# design.net
KiCad netlist of a schematic drawn in Altium Designer
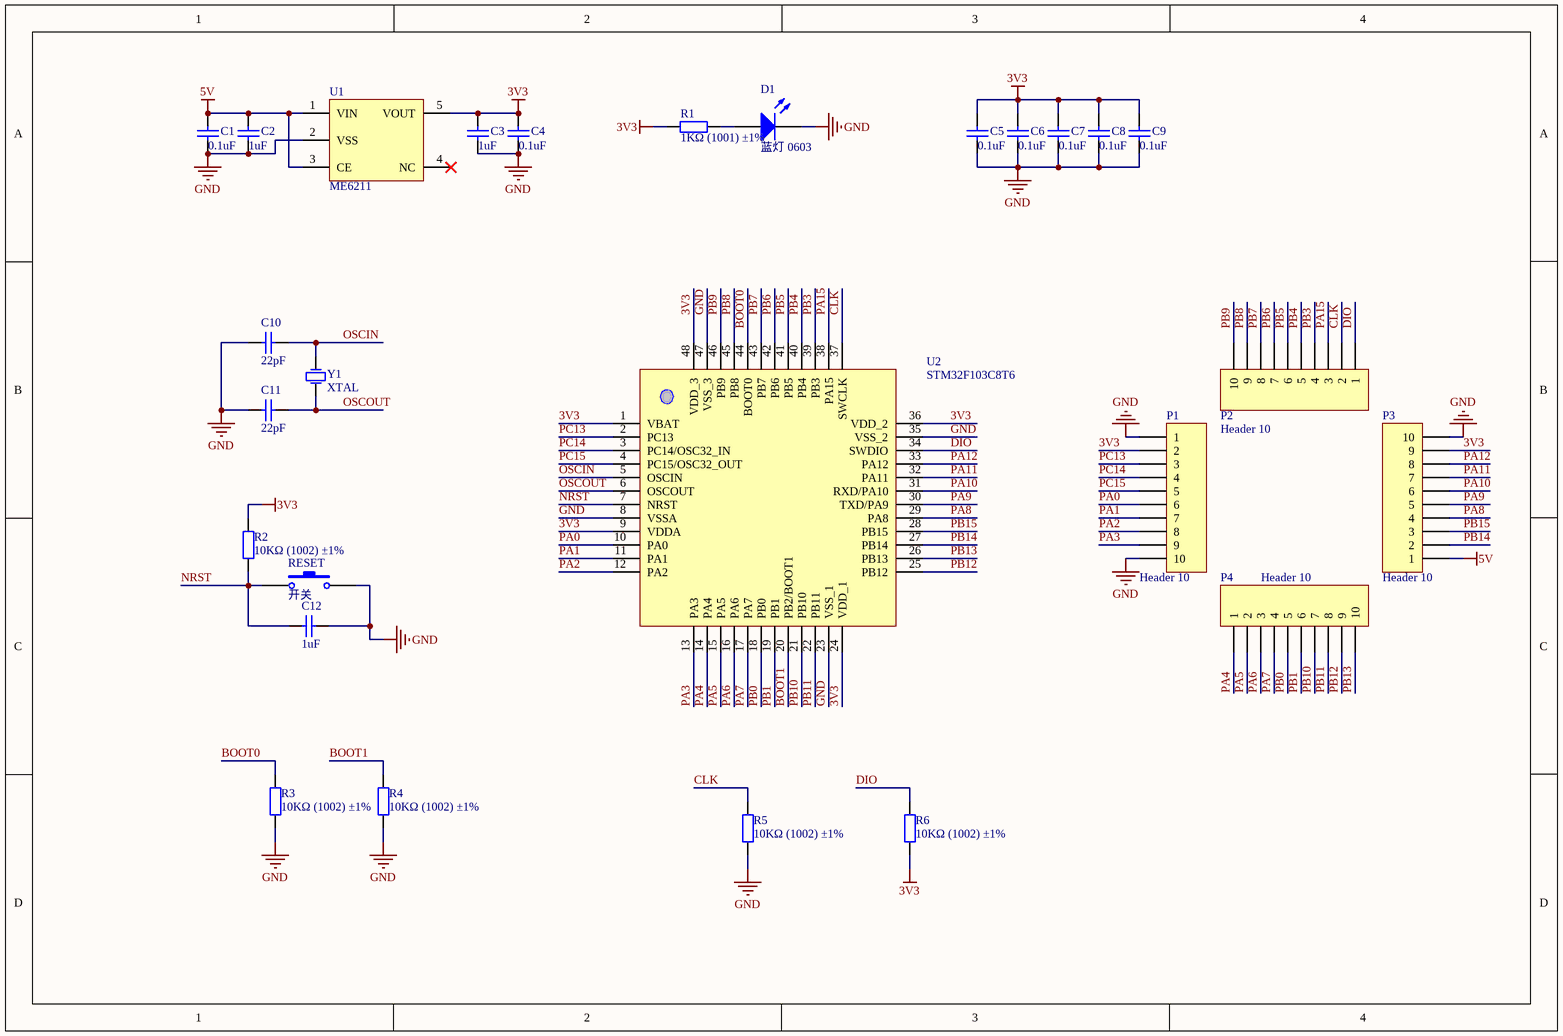
[diagram p0: 原理图.SchDoc]

(export (version "E")
  (design (tool "Eeschema 10.0.6"))
  (components
    (comp (ref "C1")
      (value "0.1uF")
      (footprint "0603_C")
      (description "贴片电容")
      (fields (field (name "Comment") "Cap"))
      (libsource (lib "Miscellaneous Devices LC (1)") (part "0603 1uF (105) 10% 50V"))
    )
    (comp (ref "C2")
      (value "1uF")
      (footprint "0603_C")
      (description "贴片电容")
      (fields (field (name "Comment") "Cap"))
      (libsource (lib "Miscellaneous Devices LC (1)") (part "0603 1uF (105) 10% 50V"))
    )
    (comp (ref "C3")
      (value "1uF")
      (footprint "0603_C")
      (description "贴片电容")
      (fields (field (name "Comment") "Cap"))
      (libsource (lib "Miscellaneous Devices LC (1)") (part "0603 1uF (105) 10% 50V"))
    )
    (comp (ref "C4")
      (value "0.1uF")
      (footprint "0603_C")
      (description "贴片电容")
      (fields (field (name "Comment") "Cap"))
      (libsource (lib "Miscellaneous Devices LC (1)") (part "0603 1uF (105) 10% 50V"))
    )
    (comp (ref "C5")
      (value "0.1uF")
      (footprint "0603_C")
      (description "贴片电容")
      (fields (field (name "Comment") "Cap"))
      (libsource (lib "Miscellaneous Devices LC (1)") (part "0603 1uF (105) 10% 50V"))
    )
    (comp (ref "C6")
      (value "0.1uF")
      (footprint "0603_C")
      (description "贴片电容")
      (fields (field (name "Comment") "Cap"))
      (libsource (lib "Miscellaneous Devices LC (1)") (part "0603 1uF (105) 10% 50V"))
    )
    (comp (ref "C7")
      (value "0.1uF")
      (footprint "0603_C")
      (description "贴片电容")
      (fields (field (name "Comment") "Cap"))
      (libsource (lib "Miscellaneous Devices LC (1)") (part "0603 1uF (105) 10% 50V"))
    )
    (comp (ref "C8")
      (value "0.1uF")
      (footprint "0603_C")
      (description "贴片电容")
      (fields (field (name "Comment") "Cap"))
      (libsource (lib "Miscellaneous Devices LC (1)") (part "0603 1uF (105) 10% 50V"))
    )
    (comp (ref "C9")
      (value "0.1uF")
      (footprint "0603_C")
      (description "贴片电容")
      (fields (field (name "Comment") "Cap"))
      (libsource (lib "Miscellaneous Devices LC (1)") (part "0603 1uF (105) 10% 50V"))
    )
    (comp (ref "C10")
      (value "22pF")
      (footprint "0603_C")
      (description "贴片电容")
      (libsource (lib "Miscellaneous Devices LC (1)") (part "0603 20pF (200) 5% 50V"))
    )
    (comp (ref "C11")
      (value "22pF")
      (footprint "0603_C")
      (description "贴片电容")
      (libsource (lib "Miscellaneous Devices LC (1)") (part "0603 20pF (200) 5% 50V"))
    )
    (comp (ref "C12")
      (value "1uF")
      (footprint "0603_C")
      (description "贴片电容")
      (fields (field (name "Comment") "Cap"))
      (libsource (lib "Miscellaneous Devices LC (1)") (part "0603 1uF (105) 10% 50V"))
    )
    (comp (ref "D1")
      (value "蓝灯 0603")
      (footprint "0603_LED_S1")
      (description "发光二极管")
      (libsource (lib "Miscellaneous Devices LC (1)") (part "0603 蓝灯"))
    )
    (comp (ref "P1")
      (value "Header 10")
      (footprint "MH10")
      (description "Header, 10-Pin")
      (fields (field (name "PUBLISHER") "Altium Limited"))
      (libsource (lib "Miscellaneous Connectors") (part "Header 10"))
    )
    (comp (ref "P2")
      (value "Header 10")
      (footprint "MH10")
      (description "Header, 10-Pin")
      (fields (field (name "PUBLISHER") "Altium Limited"))
      (libsource (lib "") (part "Header 10_1"))
    )
    (comp (ref "P3")
      (value "Header 10")
      (footprint "MH10")
      (description "Header, 10-Pin")
      (fields (field (name "PUBLISHER") "Altium Limited"))
      (libsource (lib "") (part "Header 10_3"))
    )
    (comp (ref "P4")
      (value "Header 10")
      (footprint "MH10")
      (description "Header, 10-Pin")
      (fields (field (name "PUBLISHER") "Altium Limited"))
      (libsource (lib "") (part "Header 10_2"))
    )
    (comp (ref "R1")
      (value "1KΩ (1001) ±1%")
      (footprint "0603_R")
      (description "贴片电阻")
      (libsource (lib "Miscellaneous Devices LC (1)") (part "0603 1KΩ (1001) 1%"))
    )
    (comp (ref "R2")
      (value "10KΩ (1002) ±1%")
      (footprint "0603_R")
      (description "贴片电阻")
      (libsource (lib "Miscellaneous Devices LC (1)") (part "0603 10KΩ (1002) 1%"))
    )
    (comp (ref "R3")
      (value "10KΩ (1002) ±1%")
      (footprint "0603_R")
      (description "贴片电阻")
      (libsource (lib "Miscellaneous Devices LC (1)") (part "0603 10KΩ (1002) 1%"))
    )
    (comp (ref "R4")
      (value "10KΩ (1002) ±1%")
      (footprint "0603_R")
      (description "贴片电阻")
      (libsource (lib "Miscellaneous Devices LC (1)") (part "0603 10KΩ (1002) 1%"))
    )
    (comp (ref "R5")
      (value "10KΩ (1002) ±1%")
      (footprint "0603_R")
      (description "贴片电阻")
      (libsource (lib "Miscellaneous Devices LC (1)") (part "0603 10KΩ (1002) 1%"))
    )
    (comp (ref "R6")
      (value "10KΩ (1002) ±1%")
      (footprint "0603_R")
      (description "贴片电阻")
      (libsource (lib "Miscellaneous Devices LC (1)") (part "0603 10KΩ (1002) 1%"))
    )
    (comp (ref "RESET") (value "开关") (footprint "KEY-K2") (libsource (lib "开关_按键原理图库") (part "轻触开关")))
    (comp (ref "U1") (value "ME6211") (footprint "SOT23-5") (libsource (lib "fszhang") (part "ME6211")))
    (comp (ref "U2")
      (value "STM32F103C8T6")
      (footprint "LQFP-48_7x7x05P")
      (description "STM32单片机48引脚")
      (libsource (lib "fszhang") (part "STM32F103C8T6"))
    )
    (comp (ref "Y1")
      (value "XTAL")
      (footprint "XTAL_5032")
      (description "Crystal Oscillator")
      (fields (field (name "PUBLISHER") "Altium Limited"))
      (libsource (lib "Components") (part "XTAL"))
    )
  )
  (nets
    (net (code "1") (name "/BOOT0") (class "Default")
      (node (ref "R3") (pin "2") (pinfunction "2_2") (pintype "passive"))
      (node (ref "U2") (pin "44") (pinfunction "BOOT0_44") (pintype "passive"))
    )
    (net (code "2") (name "/BOOT1") (class "Default")
      (node (ref "R4") (pin "2") (pinfunction "2_2") (pintype "passive"))
      (node (ref "U2") (pin "20") (pinfunction "PB2/BOOT1_20") (pintype "passive"))
    )
    (net (code "3") (name "/CLK") (class "Default")
      (node (ref "P2") (pin "2") (pinfunction "2_2") (pintype "passive"))
      (node (ref "R5") (pin "2") (pinfunction "2_2") (pintype "passive"))
      (node (ref "U2") (pin "37") (pinfunction "SWCLK_37") (pintype "passive"))
    )
    (net (code "4") (name "/DIO") (class "Default")
      (node (ref "P2") (pin "1") (pinfunction "1_1") (pintype "passive"))
      (node (ref "R6") (pin "2") (pinfunction "2_2") (pintype "passive"))
      (node (ref "U2") (pin "34") (pinfunction "SWDIO_34") (pintype "passive"))
    )
    (net (code "5") (name "/NRST") (class "Default")
      (node (ref "C12") (pin "1") (pinfunction "1_1") (pintype "passive"))
      (node (ref "R2") (pin "1") (pinfunction "1_1") (pintype "passive"))
      (node (ref "RESET") (pin "1") (pinfunction "1_1") (pintype "passive"))
      (node (ref "U2") (pin "7") (pinfunction "NRST_7") (pintype "passive"))
    )
    (net (code "6") (name "/OSCIN") (class "Default")
      (node (ref "C10") (pin "2") (pinfunction "2_2") (pintype "passive"))
      (node (ref "U2") (pin "5") (pinfunction "OSCIN_5") (pintype "passive"))
      (node (ref "Y1") (pin "2") (pinfunction "OSC2_2") (pintype "passive"))
    )
    (net (code "7") (name "/OSCOUT") (class "Default")
      (node (ref "C11") (pin "2") (pinfunction "2_2") (pintype "passive"))
      (node (ref "U2") (pin "6") (pinfunction "OSCOUT_6") (pintype "passive"))
      (node (ref "Y1") (pin "1") (pinfunction "OSC1_1") (pintype "passive"))
    )
    (net (code "8") (name "/PA0") (class "Default")
      (node (ref "P1") (pin "6") (pinfunction "6_6") (pintype "passive"))
      (node (ref "U2") (pin "10") (pinfunction "PA0_10") (pintype "passive"))
    )
    (net (code "9") (name "/PA1") (class "Default")
      (node (ref "P1") (pin "7") (pinfunction "7_7") (pintype "passive"))
      (node (ref "U2") (pin "11") (pinfunction "PA1_11") (pintype "passive"))
    )
    (net (code "10") (name "/PA2") (class "Default")
      (node (ref "P1") (pin "8") (pinfunction "8_8") (pintype "passive"))
      (node (ref "U2") (pin "12") (pinfunction "PA2_12") (pintype "passive"))
    )
    (net (code "11") (name "/PA3") (class "Default")
      (node (ref "P1") (pin "9") (pinfunction "9_9") (pintype "passive"))
      (node (ref "U2") (pin "13") (pinfunction "PA3_13") (pintype "passive"))
    )
    (net (code "12") (name "/PA4") (class "Default")
      (node (ref "P4") (pin "1") (pinfunction "1_1") (pintype "passive"))
      (node (ref "U2") (pin "14") (pinfunction "PA4_14") (pintype "passive"))
    )
    (net (code "13") (name "/PA5") (class "Default")
      (node (ref "P4") (pin "2") (pinfunction "2_2") (pintype "passive"))
      (node (ref "U2") (pin "15") (pinfunction "PA5_15") (pintype "passive"))
    )
    (net (code "14") (name "/PA6") (class "Default")
      (node (ref "P4") (pin "3") (pinfunction "3_3") (pintype "passive"))
      (node (ref "U2") (pin "16") (pinfunction "PA6_16") (pintype "passive"))
    )
    (net (code "15") (name "/PA7") (class "Default")
      (node (ref "P4") (pin "4") (pinfunction "4_4") (pintype "passive"))
      (node (ref "U2") (pin "17") (pinfunction "PA7_17") (pintype "passive"))
    )
    (net (code "16") (name "/PA8") (class "Default")
      (node (ref "P3") (pin "4") (pinfunction "4_4") (pintype "passive"))
      (node (ref "U2") (pin "29") (pinfunction "PA8_29") (pintype "passive"))
    )
    (net (code "17") (name "/PA9") (class "Default")
      (node (ref "P3") (pin "5") (pinfunction "5_5") (pintype "passive"))
      (node (ref "U2") (pin "30") (pinfunction "TXD/PA9_30") (pintype "passive"))
    )
    (net (code "18") (name "/PA10") (class "Default")
      (node (ref "P3") (pin "6") (pinfunction "6_6") (pintype "passive"))
      (node (ref "U2") (pin "31") (pinfunction "RXD/PA10_31") (pintype "passive"))
    )
    (net (code "19") (name "/PA11") (class "Default")
      (node (ref "P3") (pin "7") (pinfunction "7_7") (pintype "passive"))
      (node (ref "U2") (pin "32") (pinfunction "PA11_32") (pintype "passive"))
    )
    (net (code "20") (name "/PA12") (class "Default")
      (node (ref "P3") (pin "8") (pinfunction "8_8") (pintype "passive"))
      (node (ref "U2") (pin "33") (pinfunction "PA12_33") (pintype "passive"))
    )
    (net (code "21") (name "/PA15") (class "Default")
      (node (ref "P2") (pin "3") (pinfunction "3_3") (pintype "passive"))
      (node (ref "U2") (pin "38") (pinfunction "PA15_38") (pintype "passive"))
    )
    (net (code "22") (name "/PB0") (class "Default")
      (node (ref "P4") (pin "5") (pinfunction "5_5") (pintype "passive"))
      (node (ref "U2") (pin "18") (pinfunction "PB0_18") (pintype "passive"))
    )
    (net (code "23") (name "/PB1") (class "Default")
      (node (ref "P4") (pin "6") (pinfunction "6_6") (pintype "passive"))
      (node (ref "U2") (pin "19") (pinfunction "PB1_19") (pintype "passive"))
    )
    (net (code "24") (name "/PB3") (class "Default")
      (node (ref "P2") (pin "4") (pinfunction "4_4") (pintype "passive"))
      (node (ref "U2") (pin "39") (pinfunction "PB3_39") (pintype "passive"))
    )
    (net (code "25") (name "/PB4") (class "Default")
      (node (ref "P2") (pin "5") (pinfunction "5_5") (pintype "passive"))
      (node (ref "U2") (pin "40") (pinfunction "PB4_40") (pintype "passive"))
    )
    (net (code "26") (name "/PB5") (class "Default")
      (node (ref "P2") (pin "6") (pinfunction "6_6") (pintype "passive"))
      (node (ref "U2") (pin "41") (pinfunction "PB5_41") (pintype "passive"))
    )
    (net (code "27") (name "/PB6") (class "Default")
      (node (ref "P2") (pin "7") (pinfunction "7_7") (pintype "passive"))
      (node (ref "U2") (pin "42") (pinfunction "PB6_42") (pintype "passive"))
    )
    (net (code "28") (name "/PB7") (class "Default")
      (node (ref "P2") (pin "8") (pinfunction "8_8") (pintype "passive"))
      (node (ref "U2") (pin "43") (pinfunction "PB7_43") (pintype "passive"))
    )
    (net (code "29") (name "/PB8") (class "Default")
      (node (ref "P2") (pin "9") (pinfunction "9_9") (pintype "passive"))
      (node (ref "U2") (pin "45") (pinfunction "PB8_45") (pintype "passive"))
    )
    (net (code "30") (name "/PB9") (class "Default")
      (node (ref "P2") (pin "10") (pinfunction "10_10") (pintype "passive"))
      (node (ref "U2") (pin "46") (pinfunction "PB9_46") (pintype "passive"))
    )
    (net (code "31") (name "/PB10") (class "Default")
      (node (ref "P4") (pin "7") (pinfunction "7_7") (pintype "passive"))
      (node (ref "U2") (pin "21") (pinfunction "PB10_21") (pintype "passive"))
    )
    (net (code "32") (name "/PB11") (class "Default")
      (node (ref "P4") (pin "8") (pinfunction "8_8") (pintype "passive"))
      (node (ref "U2") (pin "22") (pinfunction "PB11_22") (pintype "passive"))
    )
    (net (code "33") (name "/PB12") (class "Default")
      (node (ref "P4") (pin "9") (pinfunction "9_9") (pintype "passive"))
      (node (ref "U2") (pin "25") (pinfunction "PB12_25") (pintype "passive"))
    )
    (net (code "34") (name "/PB13") (class "Default")
      (node (ref "P4") (pin "10") (pinfunction "10_10") (pintype "passive"))
      (node (ref "U2") (pin "26") (pinfunction "PB13_26") (pintype "passive"))
    )
    (net (code "35") (name "/PB14") (class "Default")
      (node (ref "P3") (pin "2") (pinfunction "2_2") (pintype "passive"))
      (node (ref "U2") (pin "27") (pinfunction "PB14_27") (pintype "passive"))
    )
    (net (code "36") (name "/PB15") (class "Default")
      (node (ref "P3") (pin "3") (pinfunction "3_3") (pintype "passive"))
      (node (ref "U2") (pin "28") (pinfunction "PB15_28") (pintype "passive"))
    )
    (net (code "37") (name "/PC13") (class "Default")
      (node (ref "P1") (pin "3") (pinfunction "3_3") (pintype "passive"))
      (node (ref "U2") (pin "2") (pinfunction "PC13_2") (pintype "passive"))
    )
    (net (code "38") (name "/PC14") (class "Default")
      (node (ref "P1") (pin "4") (pinfunction "4_4") (pintype "passive"))
      (node (ref "U2") (pin "3") (pinfunction "PC14/OSC32_IN_3") (pintype "passive"))
    )
    (net (code "39") (name "/PC15") (class "Default")
      (node (ref "P1") (pin "5") (pinfunction "5_5") (pintype "passive"))
      (node (ref "U2") (pin "4") (pinfunction "PC15/OSC32_OUT_4") (pintype "passive"))
    )
    (net (code "40") (name "3V3") (class "Default")
      (node (ref "C3") (pin "2") (pinfunction "2_2") (pintype "passive"))
      (node (ref "C4") (pin "2") (pinfunction "2_2") (pintype "passive"))
      (node (ref "C5") (pin "2") (pinfunction "2_2") (pintype "passive"))
      (node (ref "C6") (pin "2") (pinfunction "2_2") (pintype "passive"))
      (node (ref "C7") (pin "2") (pinfunction "2_2") (pintype "passive"))
      (node (ref "C8") (pin "2") (pinfunction "2_2") (pintype "passive"))
      (node (ref "C9") (pin "2") (pinfunction "2_2") (pintype "passive"))
      (node (ref "P1") (pin "2") (pinfunction "2_2") (pintype "passive"))
      (node (ref "P3") (pin "9") (pinfunction "9_9") (pintype "passive"))
      (node (ref "R1") (pin "1") (pinfunction "1_1") (pintype "passive"))
      (node (ref "R2") (pin "2") (pinfunction "2_2") (pintype "passive"))
      (node (ref "R6") (pin "1") (pinfunction "1_1") (pintype "passive"))
      (node (ref "U1") (pin "5") (pinfunction "VOUT_5") (pintype "passive"))
      (node (ref "U2") (pin "1") (pinfunction "VBAT_1") (pintype "passive"))
      (node (ref "U2") (pin "24") (pinfunction "VDD_1_24") (pintype "passive"))
      (node (ref "U2") (pin "36") (pinfunction "VDD_2_36") (pintype "passive"))
      (node (ref "U2") (pin "48") (pinfunction "VDD_3_48") (pintype "passive"))
      (node (ref "U2") (pin "9") (pinfunction "VDDA_9") (pintype "passive"))
    )
    (net (code "41") (name "5V") (class "Default")
      (node (ref "C1") (pin "2") (pinfunction "2_2") (pintype "passive"))
      (node (ref "C2") (pin "2") (pinfunction "2_2") (pintype "passive"))
      (node (ref "P3") (pin "1") (pinfunction "1_1") (pintype "passive"))
      (node (ref "U1") (pin "1") (pinfunction "VIN_1") (pintype "passive"))
      (node (ref "U1") (pin "3") (pinfunction "CE_3") (pintype "passive"))
    )
    (net (code "42") (name "GND") (class "Default")
      (node (ref "C1") (pin "1") (pinfunction "1_1") (pintype "passive"))
      (node (ref "C10") (pin "1") (pinfunction "1_1") (pintype "passive"))
      (node (ref "C11") (pin "1") (pinfunction "1_1") (pintype "passive"))
      (node (ref "C12") (pin "2") (pinfunction "2_2") (pintype "passive"))
      (node (ref "C2") (pin "1") (pinfunction "1_1") (pintype "passive"))
      (node (ref "C3") (pin "1") (pinfunction "1_1") (pintype "passive"))
      (node (ref "C4") (pin "1") (pinfunction "1_1") (pintype "passive"))
      (node (ref "C5") (pin "1") (pinfunction "1_1") (pintype "passive"))
      (node (ref "C6") (pin "1") (pinfunction "1_1") (pintype "passive"))
      (node (ref "C7") (pin "1") (pinfunction "1_1") (pintype "passive"))
      (node (ref "C8") (pin "1") (pinfunction "1_1") (pintype "passive"))
      (node (ref "C9") (pin "1") (pinfunction "1_1") (pintype "passive"))
      (node (ref "D1") (pin "K") (pinfunction "K_K") (pintype "passive"))
      (node (ref "P1") (pin "1") (pinfunction "1_1") (pintype "passive"))
      (node (ref "P1") (pin "10") (pinfunction "10_10") (pintype "passive"))
      (node (ref "P3") (pin "10") (pinfunction "10_10") (pintype "passive"))
      (node (ref "R3") (pin "1") (pinfunction "1_1") (pintype "passive"))
      (node (ref "R4") (pin "1") (pinfunction "1_1") (pintype "passive"))
      (node (ref "R5") (pin "1") (pinfunction "1_1") (pintype "passive"))
      (node (ref "RESET") (pin "2") (pinfunction "2_2") (pintype "passive"))
      (node (ref "U1") (pin "2") (pinfunction "VSS_2") (pintype "passive"))
      (node (ref "U2") (pin "23") (pinfunction "VSS_1_23") (pintype "passive"))
      (node (ref "U2") (pin "35") (pinfunction "VSS_2_35") (pintype "passive"))
      (node (ref "U2") (pin "47") (pinfunction "VSS_3_47") (pintype "passive"))
      (node (ref "U2") (pin "8") (pinfunction "VSSA_8") (pintype "passive"))
    )
    (net (code "43") (name "Net-(D1-PadA)") (class "Default")
      (node (ref "D1") (pin "A") (pinfunction "A_A") (pintype "passive"))
      (node (ref "R1") (pin "2") (pinfunction "2_2") (pintype "passive"))
    )
    (net (code "44") (name "unconnected-(U1-NC-Pad4)") (class "Default")
      (node (ref "U1") (pin "4") (pinfunction "NC_4") (pintype "passive+no_connect"))
    )
  )
)
